# DISPLAY.net
KiCad netlist of a schematic drawn in Altium Designer
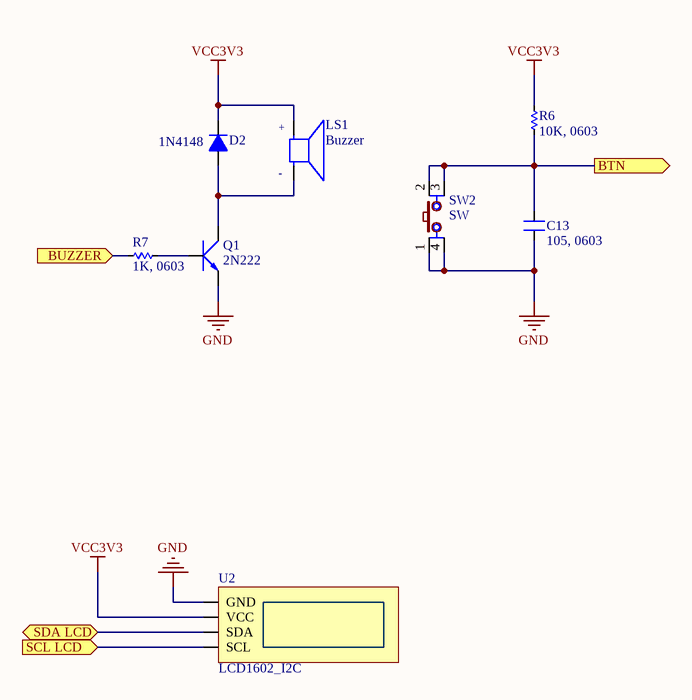
[diagram p0: DISPLAY.SchDoc]

(export (version "E")
  (design (tool "Eeschema 10.0.6"))
  (components
    (comp (ref "C13")
      (value "105, 0603")
      (footprint "SM-0603")
      (description "Cap SMD")
      (libsource (lib "KhanhBK_Library_4") (part "CM"))
    )
    (comp (ref "D2")
      (value "1N4148")
      (footprint "D0.5A")
      (description "D0.5A")
      (libsource (lib "KhanhBK_SCH_Library_2") (part "D0.5A"))
    )
    (comp (ref "LS1")
      (value "Buzzer")
      (footprint "XDCR_AI-1027-TWT-3V-R")
      (fields (field (name "MF") "{'manufacturer': u'PUI Audio,'}") (field (name "MP") "AI-1027-TWT-3V-R"))
      (libsource (lib "SnapEDA_Library") (part "AI-1027-TWT-3V-R"))
    )
    (comp (ref "Q1")
      (value "2N222")
      (footprint "TO92-123")
      (description "NPN 600mW, ECB")
      (libsource (lib "KhanhBK_SCH_Library_1") (part "2N222"))
    )
    (comp (ref "R6")
      (value "10K, 0603")
      (footprint "RES-SMD-0603")
      (description "Resistor")
      (fields
        (field (name "MANUFACTURER") "Generic Components")
        (field (name "PUBLISHER") "Altium Hobart Technology Centre")
      )
      (libsource (lib "KhanhBK_SCH_Library_1") (part "Res-SMD"))
    )
    (comp (ref "R7")
      (value "1K, 0603")
      (footprint "RES-SMD-0603")
      (description "Resistor")
      (fields
        (field (name "MANUFACTURER") "Generic Components")
        (field (name "PUBLISHER") "Altium Hobart Technology Centre")
      )
      (libsource (lib "KhanhBK_SCH_Library_1") (part "Res-SMD"))
    )
    (comp (ref "SW2")
      (value "SW")
      (footprint "SW2-SMD")
      (description "Switch button 4 pin")
      (libsource (lib "KhanhBK_SCH_Library_1") (part "SW4"))
    )
    (comp (ref "U2")
      (value "LCD1602_I2C")
      (description "Module LCD1602 I2C")
      (libsource (lib "MyComponets") (part "LCD1602_I2C"))
    )
  )
  (nets
    (net (code "1") (name "/BTN") (class "Default")
      (node (ref "C13") (pin "2") (pinfunction "2_2") (pintype "passive"))
      (node (ref "R6") (pin "1") (pinfunction "1_1") (pintype "passive"))
      (node (ref "SW2") (pin "2") (pinfunction "2_2") (pintype "passive"))
      (node (ref "SW2") (pin "3") (pinfunction "3_3") (pintype "passive"))
    )
    (net (code "2") (name "/BUZZER") (class "Default")
      (node (ref "R7") (pin "2") (pinfunction "2_2") (pintype "passive"))
    )
    (net (code "3") (name "/SCL LCD") (class "Default")
      (node (ref "U2") (pin "4") (pinfunction "SCL_4") (pintype "passive"))
    )
    (net (code "4") (name "/SDA LCD") (class "Default")
      (node (ref "U2") (pin "3") (pinfunction "SDA_3") (pintype "passive"))
    )
    (net (code "5") (name "GND") (class "Default")
      (node (ref "C13") (pin "1") (pinfunction "1_1") (pintype "passive"))
      (node (ref "Q1") (pin "1") (pinfunction "E_1") (pintype "passive"))
      (node (ref "SW2") (pin "1") (pintype "passive"))
      (node (ref "SW2") (pin "4") (pinfunction "4_4") (pintype "passive"))
      (node (ref "U2") (pin "1") (pinfunction "GND_1") (pintype "passive"))
    )
    (net (code "6") (name "Net-(D2-A)") (class "Default")
      (node (ref "D2") (pin "1") (pinfunction "A_1") (pintype "passive"))
      (node (ref "LS1") (pin "N") (pinfunction "N_N") (pintype "passive"))
      (node (ref "Q1") (pin "3") (pinfunction "C_3") (pintype "passive"))
    )
    (net (code "7") (name "Net-(Q1-B)") (class "Default")
      (node (ref "Q1") (pin "2") (pinfunction "B_2") (pintype "passive"))
      (node (ref "R7") (pin "1") (pinfunction "1_1") (pintype "passive"))
    )
    (net (code "8") (name "VCC3V3") (class "Default")
      (node (ref "D2") (pin "2") (pinfunction "K_2") (pintype "passive"))
      (node (ref "LS1") (pin "P") (pinfunction "P_P") (pintype "passive"))
      (node (ref "R6") (pin "2") (pinfunction "2_2") (pintype "passive"))
      (node (ref "U2") (pin "2") (pinfunction "VCC_2") (pintype "passive"))
    )
  )
)
